# 04_Neo6M.net
KiCad netlist of a schematic drawn in Altium Designer
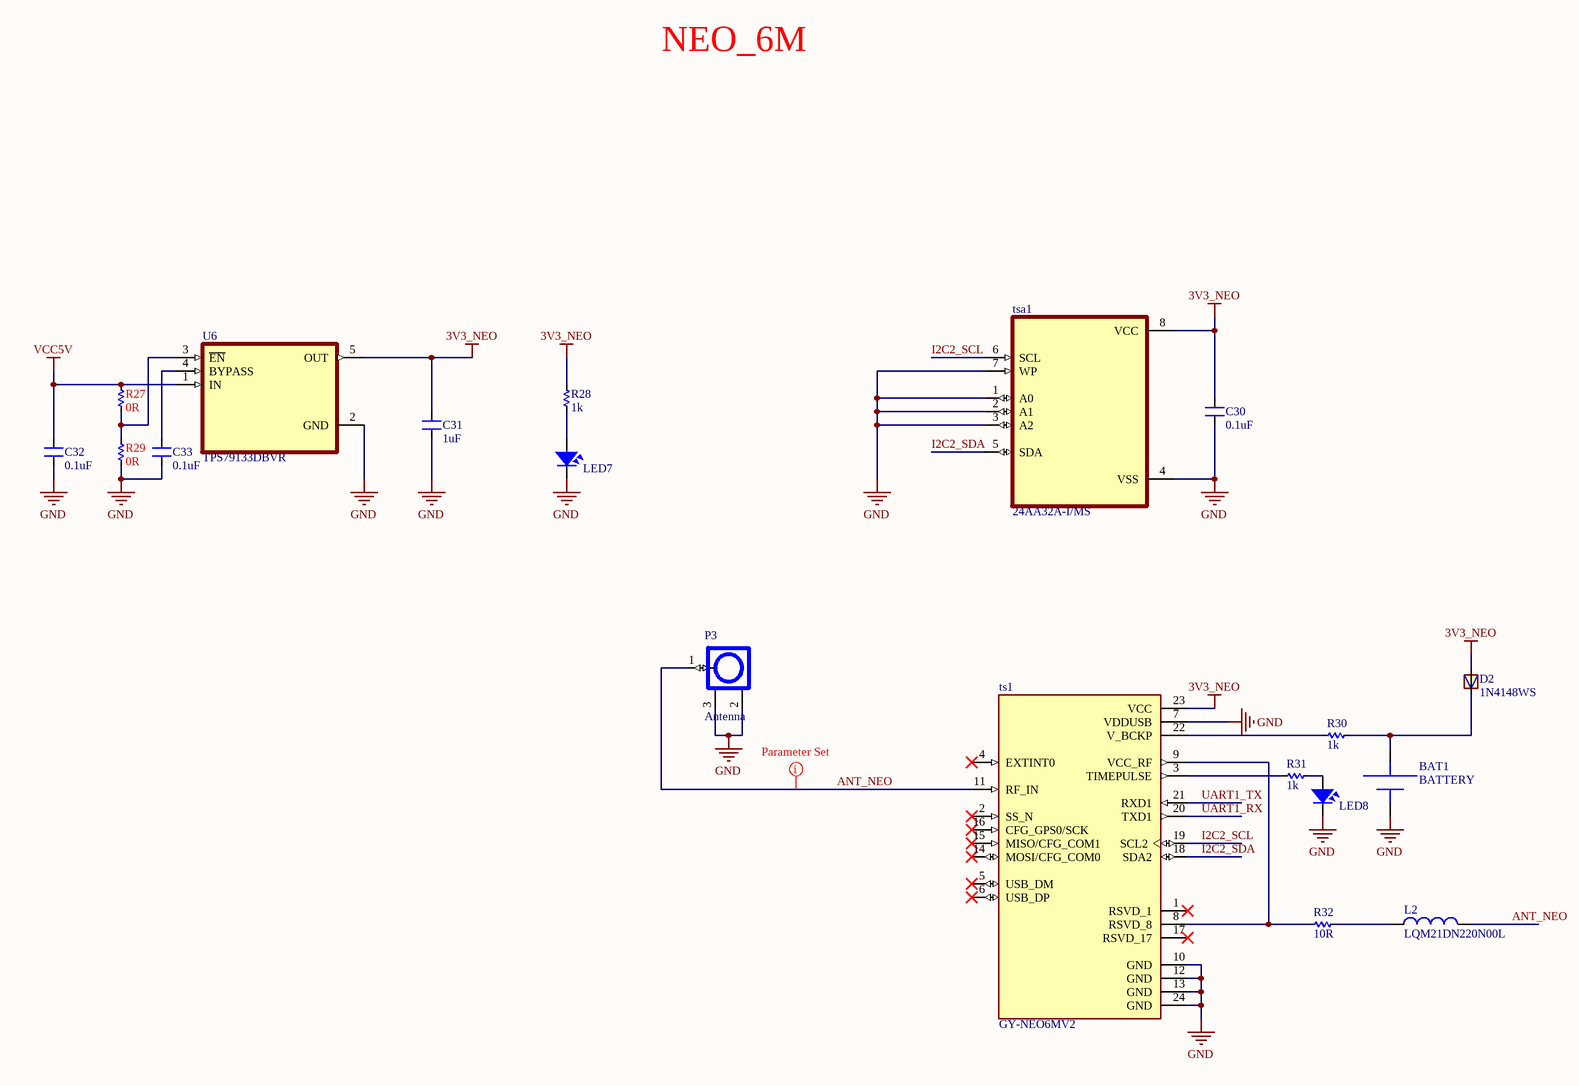
[diagram p0: 04 Neo6M.SchDoc]

(export (version "E")
  (design (tool "Eeschema 10.0.6"))
  (components
    (comp (ref "BAT1")
      (value "BATTERY")
      (footprint "BATTERY_CON")
      (libsource (lib "MinhNguyenCao") (part "BATTERY"))
    )
    (comp (ref "C30")
      (value "0.1uF")
      (footprint "HuanHaui_FEETEAM:C 0603")
      (description "16V")
      (libsource (lib "HuanHaui_FEETEAM") (part "CAP_SMD"))
    )
    (comp (ref "C31")
      (value "1uF")
      (footprint "HuanHaui_FEETEAM:C 0603")
      (description "16V")
      (libsource (lib "HuanHaui_FEETEAM") (part "CAP_SMD"))
    )
    (comp (ref "C32")
      (value "0.1uF")
      (footprint "HuanHaui_FEETEAM:C 0603")
      (description "16V")
      (libsource (lib "HuanHaui_FEETEAM") (part "CAP_SMD"))
    )
    (comp (ref "C33")
      (value "0.1uF")
      (footprint "HuanHaui_FEETEAM:C 0603")
      (description "16V")
      (libsource (lib "HuanHaui_FEETEAM") (part "CAP_SMD"))
    )
    (comp (ref "D2")
      (value "1N4148WS")
      (footprint "SOD323")
      (description "Small Signal Diode, SOD-323F, 100V, 0.15A, 150Â°C")
      (fields (field (name "MF") "Diotec Semiconductor"))
      (libsource (lib "MinhNguyenCao") (part "1N4148WS"))
    )
    (comp (ref "L2")
      (value "LQM21DN220N00L")
      (footprint "INDC2012X145N")
      (description "Inductor with Inductance: 22uH Tol. +/-30%, Package: 0805 (2012)")
      (fields (field (name "MF") "Murata"))
      (libsource (lib "MinhNguyenCao") (part "LQM21DN220N00L"))
    )
    (comp (ref "LED7")
      (value "LED")
      (footprint "My Library:LED-0603")
      (libsource (lib "My Library") (part "LED SMD"))
    )
    (comp (ref "LED8")
      (value "LED")
      (footprint "My Library:LED-0603")
      (libsource (lib "My Library") (part "LED SMD"))
    )
    (comp (ref "P3")
      (value "Antenna")
      (footprint "IPXS")
      (description "Antenna GSM GPS")
      (libsource (lib "My Library") (part "IPXSx66"))
    )
    (comp (ref "R27")
      (value "0R")
      (footprint "HuanHaui_FEETEAM:RES-SMD-0603")
      (description "RES_SMD")
      (fields
        (field (name "MANUFACTURER") "Generic Components")
        (field (name "PUBLISHER") "Altium Hobart Technology Centre")
      )
      (libsource (lib "HuanHaui_FEETEAM") (part "Res-SMD"))
    )
    (comp (ref "R28")
      (value "1k")
      (footprint "HuanHaui_FEETEAM:RES-SMD-0603")
      (description "RES_SMD")
      (fields
        (field (name "MANUFACTURER") "Generic Components")
        (field (name "PUBLISHER") "Altium Hobart Technology Centre")
      )
      (libsource (lib "HuanHaui_FEETEAM") (part "Res-SMD"))
    )
    (comp (ref "R29")
      (value "0R")
      (footprint "HuanHaui_FEETEAM:RES-SMD-0603")
      (description "RES_SMD")
      (fields
        (field (name "MANUFACTURER") "Generic Components")
        (field (name "PUBLISHER") "Altium Hobart Technology Centre")
      )
      (libsource (lib "HuanHaui_FEETEAM") (part "Res-SMD"))
    )
    (comp (ref "R30")
      (value "1k")
      (footprint "HuanHaui_FEETEAM:RES-SMD-0603")
      (description "RES_SMD")
      (fields
        (field (name "MANUFACTURER") "Generic Components")
        (field (name "PUBLISHER") "Altium Hobart Technology Centre")
      )
      (libsource (lib "HuanHaui_FEETEAM") (part "Res-SMD"))
    )
    (comp (ref "R31")
      (value "1k")
      (footprint "HuanHaui_FEETEAM:RES-SMD-0603")
      (description "RES_SMD")
      (fields
        (field (name "MANUFACTURER") "Generic Components")
        (field (name "PUBLISHER") "Altium Hobart Technology Centre")
      )
      (libsource (lib "HuanHaui_FEETEAM") (part "Res-SMD"))
    )
    (comp (ref "R32")
      (value "10R")
      (footprint "HuanHaui_FEETEAM:RES-SMD-0603")
      (description "RES_SMD")
      (fields
        (field (name "MANUFACTURER") "Generic Components")
        (field (name "PUBLISHER") "Altium Hobart Technology Centre")
      )
      (libsource (lib "HuanHaui_FEETEAM") (part "Res-SMD"))
    )
    (comp (ref "ts1")
      (value "GY-NEO6MV2")
      (footprint "XCVR_GY-NEO6MV2")
      (fields (field (name "MF") "Ublox"))
      (libsource (lib "MinhNguyenCao") (part "GY-NEO6MV2"))
    )
    (comp (ref "tsa1")
      (value "24AA32A-I/MS")
      (footprint "SOP65P490X110-8N")
      (description "EEPROM Memory IC 32Kb _4K x 8_ IÂ²C 400kHz 900ns 8-MSOP")
      (fields (field (name "MF") "Microchip"))
      (libsource (lib "MinhNguyenCao") (part "24AA32A-I/MS"))
    )
    (comp (ref "U6")
      (value "TPS79133DBVR")
      (footprint "SOT95P280X145-5N")
      (description "100-mA, low-noise, low-dropout voltage regulator with enable")
      (fields (field (name "MF") "Texas Instruments"))
      (libsource (lib "MinhNguyenCao") (part "TPS79133DBVR"))
    )
  )
  (nets
    (net (code "1") (name "/ANT_NEO") (class "Default")
      (node (ref "L2") (pin "2") (pinfunction "2_2") (pintype "passive"))
      (node (ref "P3") (pin "1") (pintype "bidirectional"))
      (node (ref "ts1") (pin "11") (pinfunction "RF_IN_11") (pintype "input"))
    )
    (net (code "2") (name "/I2C2_SCL") (class "Default")
      (node (ref "ts1") (pin "19") (pinfunction "SCL2_19") (pintype "bidirectional"))
      (node (ref "tsa1") (pin "6") (pinfunction "SCL_6") (pintype "input"))
    )
    (net (code "3") (name "/I2C2_SDA") (class "Default")
      (node (ref "ts1") (pin "18") (pinfunction "SDA2_18") (pintype "bidirectional"))
      (node (ref "tsa1") (pin "5") (pinfunction "SDA_5") (pintype "bidirectional"))
    )
    (net (code "4") (name "/UART1_RX") (class "Default")
      (node (ref "ts1") (pin "20") (pinfunction "TXD1_20") (pintype "output"))
    )
    (net (code "5") (name "/UART1_TX") (class "Default")
      (node (ref "ts1") (pin "21") (pinfunction "RXD1_21") (pintype "input"))
    )
    (net (code "6") (name "3V3_NEO") (class "Default")
      (node (ref "C30") (pin "2") (pinfunction "2_2") (pintype "passive"))
      (node (ref "C31") (pin "2") (pinfunction "2_2") (pintype "passive"))
      (node (ref "D2") (pin "A") (pinfunction "A_A") (pintype "passive"))
      (node (ref "R28") (pin "1") (pinfunction "1_1") (pintype "passive"))
      (node (ref "U6") (pin "5") (pinfunction "OUT_5") (pintype "output"))
      (node (ref "ts1") (pin "23") (pinfunction "VCC_23") (pintype "power_in"))
      (node (ref "tsa1") (pin "8") (pinfunction "VCC_8") (pintype "power_in"))
    )
    (net (code "7") (name "GND") (class "Default")
      (node (ref "BAT1") (pin "0") (pinfunction "0_0") (pintype "passive"))
      (node (ref "C30") (pin "1") (pinfunction "1_1") (pintype "passive"))
      (node (ref "C31") (pin "1") (pinfunction "1_1") (pintype "passive"))
      (node (ref "C32") (pin "1") (pinfunction "1_1") (pintype "passive"))
      (node (ref "C33") (pin "1") (pinfunction "1_1") (pintype "passive"))
      (node (ref "LED7") (pin "2") (pinfunction "2_2") (pintype "passive"))
      (node (ref "LED8") (pin "2") (pinfunction "2_2") (pintype "passive"))
      (node (ref "P3") (pin "2") (pintype "passive"))
      (node (ref "P3") (pin "3") (pintype "passive"))
      (node (ref "R29") (pin "2") (pinfunction "2_2") (pintype "passive"))
      (node (ref "U6") (pin "2") (pinfunction "GND_2") (pintype "power_in"))
      (node (ref "ts1") (pin "10") (pinfunction "GND_10") (pintype "power_in"))
      (node (ref "ts1") (pin "12") (pinfunction "GND_12") (pintype "power_in"))
      (node (ref "ts1") (pin "13") (pinfunction "GND_13") (pintype "power_in"))
      (node (ref "ts1") (pin "24") (pinfunction "GND_24") (pintype "power_in"))
      (node (ref "ts1") (pin "7") (pinfunction "VDDUSB_7") (pintype "power_in"))
      (node (ref "tsa1") (pin "1") (pinfunction "A0_1") (pintype "bidirectional"))
      (node (ref "tsa1") (pin "2") (pinfunction "A1_2") (pintype "bidirectional"))
      (node (ref "tsa1") (pin "3") (pinfunction "A2_3") (pintype "bidirectional"))
      (node (ref "tsa1") (pin "4") (pinfunction "VSS_4") (pintype "power_in"))
      (node (ref "tsa1") (pin "7") (pinfunction "WP_7") (pintype "input"))
    )
    (net (code "8") (name "Net-(BAT1-Pad1)") (class "Default")
      (node (ref "BAT1") (pin "1") (pinfunction "1_1") (pintype "passive"))
      (node (ref "D2") (pin "C") (pinfunction "C_C") (pintype "passive"))
      (node (ref "R30") (pin "1") (pinfunction "1_1") (pintype "passive"))
    )
    (net (code "9") (name "Net-(L2-Pad1)") (class "Default")
      (node (ref "L2") (pin "1") (pinfunction "1_1") (pintype "passive"))
      (node (ref "R32") (pin "1") (pinfunction "1_1") (pintype "passive"))
    )
    (net (code "10") (name "Net-(LED7-Pad1)") (class "Default")
      (node (ref "LED7") (pin "1") (pinfunction "1_1") (pintype "passive"))
      (node (ref "R28") (pin "2") (pinfunction "2_2") (pintype "passive"))
    )
    (net (code "11") (name "Net-(LED8-Pad1)") (class "Default")
      (node (ref "LED8") (pin "1") (pinfunction "1_1") (pintype "passive"))
      (node (ref "R31") (pin "1") (pinfunction "1_1") (pintype "passive"))
    )
    (net (code "12") (name "Net-(U6-BYPASS)") (class "Default")
      (node (ref "C33") (pin "2") (pinfunction "2_2") (pintype "passive"))
      (node (ref "U6") (pin "4") (pinfunction "BYPASS_4") (pintype "input"))
    )
    (net (code "13") (name "Net-(U6-~{EN})") (class "Default")
      (node (ref "R27") (pin "2") (pinfunction "2_2") (pintype "passive"))
      (node (ref "R29") (pin "1") (pinfunction "1_1") (pintype "passive"))
      (node (ref "U6") (pin "3") (pinfunction "~{EN}_3") (pintype "input"))
    )
    (net (code "14") (name "Net-(ts1-RSVD_8)") (class "Default")
      (node (ref "R32") (pin "2") (pinfunction "2_2") (pintype "passive"))
      (node (ref "ts1") (pin "8") (pinfunction "RSVD_8_8") (pintype "passive"))
      (node (ref "ts1") (pin "9") (pinfunction "VCC_RF_9") (pintype "output"))
    )
    (net (code "15") (name "Net-(ts1-TIMEPULSE)") (class "Default")
      (node (ref "R31") (pin "2") (pinfunction "2_2") (pintype "passive"))
      (node (ref "ts1") (pin "3") (pinfunction "TIMEPULSE_3") (pintype "output"))
    )
    (net (code "16") (name "Net-(ts1-V_BCKP)") (class "Default")
      (node (ref "R30") (pin "2") (pinfunction "2_2") (pintype "passive"))
      (node (ref "ts1") (pin "22") (pinfunction "V_BCKP_22") (pintype "power_in"))
    )
    (net (code "17") (name "VCC5V") (class "Default")
      (node (ref "C32") (pin "2") (pinfunction "2_2") (pintype "passive"))
      (node (ref "R27") (pin "1") (pinfunction "1_1") (pintype "passive"))
      (node (ref "U6") (pin "1") (pinfunction "IN_1") (pintype "input"))
    )
    (net (code "18") (name "unconnected-(ts1-CFG_GPS0{slash}SCK-Pad16)") (class "Default")
      (node (ref "ts1") (pin "16") (pinfunction "CFG_GPS0/SCK_16") (pintype "input+no_connect"))
    )
    (net (code "19") (name "unconnected-(ts1-EXTINT0-Pad4)") (class "Default")
      (node (ref "ts1") (pin "4") (pinfunction "EXTINT0_4") (pintype "input+no_connect"))
    )
    (net (code "20") (name "unconnected-(ts1-MISO{slash}CFG_COM1-Pad15)") (class "Default")
      (node (ref "ts1") (pin "15") (pinfunction "MISO/CFG_COM1_15") (pintype "input+no_connect"))
    )
    (net (code "21") (name "unconnected-(ts1-MOSI{slash}CFG_COM0-Pad14)") (class "Default")
      (node (ref "ts1") (pin "14") (pinfunction "MOSI/CFG_COM0_14") (pintype "bidirectional+no_connect"))
    )
    (net (code "22") (name "unconnected-(ts1-RSVD_1-Pad1)") (class "Default")
      (node (ref "ts1") (pin "1") (pinfunction "RSVD_1_1") (pintype "passive+no_connect"))
    )
    (net (code "23") (name "unconnected-(ts1-RSVD_17-Pad17)") (class "Default")
      (node (ref "ts1") (pin "17") (pinfunction "RSVD_17_17") (pintype "passive+no_connect"))
    )
    (net (code "24") (name "unconnected-(ts1-SS_N-Pad2)") (class "Default")
      (node (ref "ts1") (pin "2") (pinfunction "SS_N_2") (pintype "input+no_connect"))
    )
    (net (code "25") (name "unconnected-(ts1-USB_DM-Pad5)") (class "Default")
      (node (ref "ts1") (pin "5") (pinfunction "USB_DM_5") (pintype "bidirectional+no_connect"))
    )
    (net (code "26") (name "unconnected-(ts1-USB_DP-Pad6)") (class "Default")
      (node (ref "ts1") (pin "6") (pinfunction "USB_DP_6") (pintype "bidirectional+no_connect"))
    )
  )
)
